# Enclosure_85x58_PBC-AW.net
KiCad netlist of a schematic drawn in EAGLE
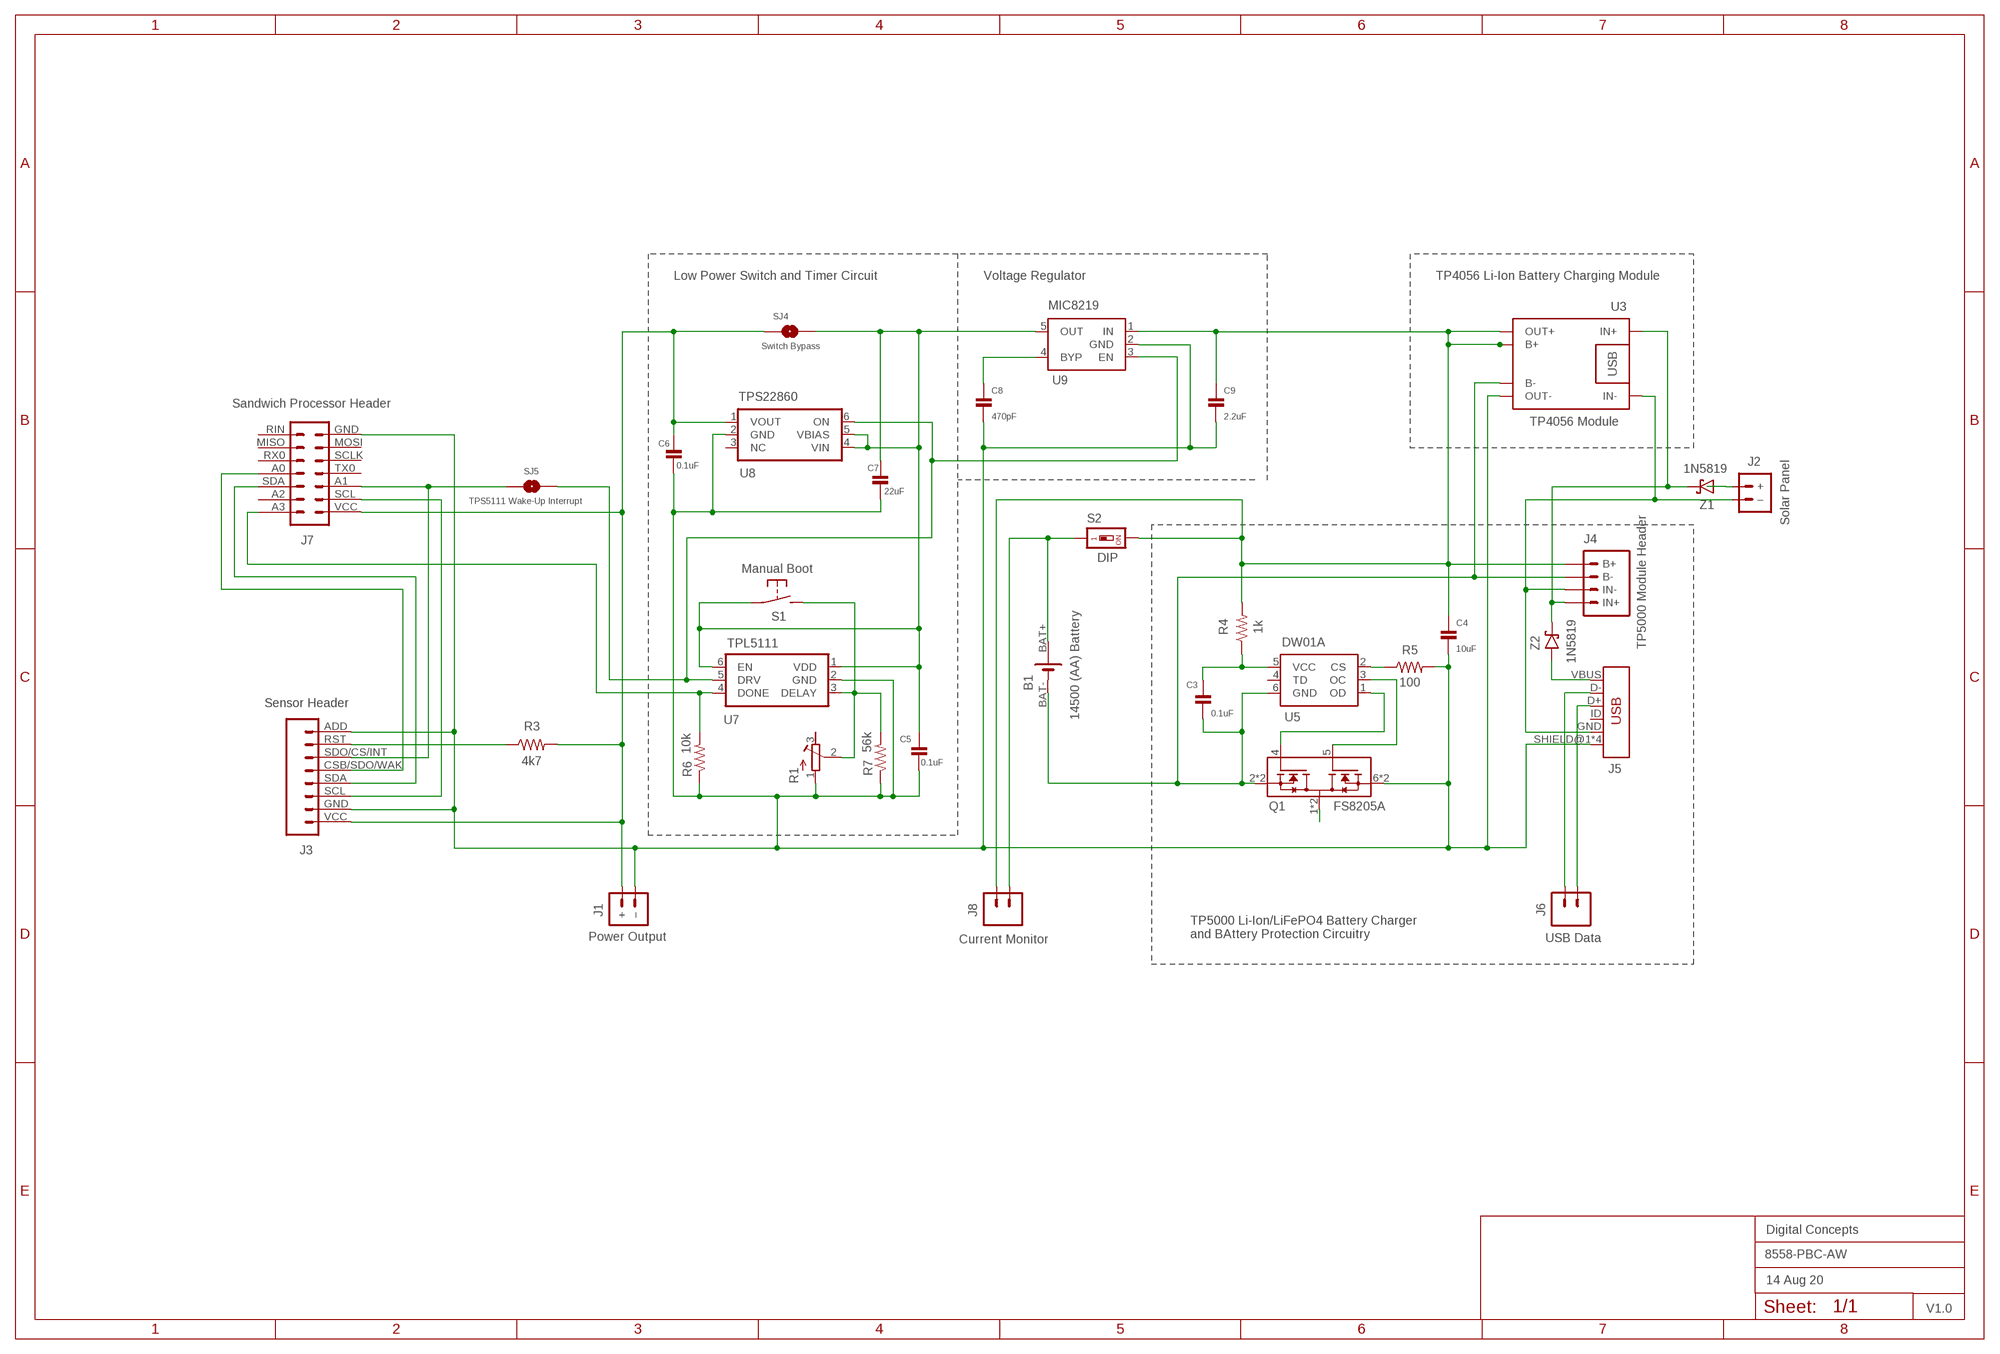
[diagram p0: schematic, sheet 1]

(export (version "E")
  (design (tool "Eeschema 10.0.6"))
  (components
    (comp (ref "B1")
      (value "14500 (AA) Battery")
      (footprint "eagle-import:BATTERY-14500")
      (libsource (lib "eagle-import") (part "BATTERY-HOLDER-14500(AA)"))
    )
    (comp (ref "C3")
      (value "0.1uF")
      (footprint "eagle-import:C0805")
      (libsource (lib "eagle-import") (part "CAPACITOR"))
    )
    (comp (ref "C4")
      (value "10uF")
      (footprint "eagle-import:C0805")
      (libsource (lib "eagle-import") (part "CAPACITOR"))
    )
    (comp (ref "C5")
      (value "0.1uF")
      (footprint "eagle-import:C0805")
      (libsource (lib "eagle-import") (part "CAPACITOR"))
    )
    (comp (ref "C6")
      (value "0.1uF")
      (footprint "eagle-import:C0805")
      (libsource (lib "eagle-import") (part "CAPACITOR"))
    )
    (comp (ref "C7")
      (value "22uF")
      (footprint "eagle-import:C0805")
      (libsource (lib "eagle-import") (part "CAPACITOR"))
    )
    (comp (ref "C8")
      (value "470pF")
      (footprint "eagle-import:C0805")
      (libsource (lib "eagle-import") (part "CAPACITOR"))
    )
    (comp (ref "C9")
      (value "2.2uF")
      (footprint "eagle-import:C0805")
      (libsource (lib "eagle-import") (part "CAPACITOR"))
    )
    (comp (ref "J1")
      (value "Power Output")
      (footprint "eagle-import:JST-PH1.25")
      (libsource (lib "eagle-import") (part "JST-PH1.25-MALE"))
    )
    (comp (ref "J2")
      (value "Solar Panel")
      (footprint "eagle-import:JST-PH2.0")
      (libsource (lib "eagle-import") (part "JST-PH2.0-MALE"))
    )
    (comp (ref "J3")
      (value "Sensor Header")
      (footprint "eagle-import:CONN_08-SENSOR")
      (libsource (lib "eagle-import") (part "HEADER-1X8-SENSOR"))
    )
    (comp (ref "J4")
      (value "TP5000 Module Header")
      (footprint "eagle-import:CONN_04-GENERIC")
      (libsource (lib "eagle-import") (part "TP5000-MODULE"))
    )
    (comp (ref "J5")
      (value "USB")
      (footprint "eagle-import:USB-MINIB")
      (libsource (lib "eagle-import") (part "USB_MINI-B_SMT"))
    )
    (comp (ref "J6")
      (value "USB Data")
      (footprint "eagle-import:CONN_02-GENERIC")
      (libsource (lib "eagle-import") (part "1X2-PIN-HEADER"))
    )
    (comp (ref "J7")
      (value "Sandwich Processor Header")
      (footprint "eagle-import:CONN_2X7-WIJNAND-PROCESSOR")
      (libsource (lib "eagle-import") (part "HEADER-2X7-SANDWICH-PROCESSOR"))
    )
    (comp (ref "J8")
      (value "JST-PH2.0-MALE-HORIZONTALJST-PTH-2")
      (footprint "eagle-import:JST-2-PTH")
      (libsource (lib "eagle-import") (part "JST-PH2.0-MALE-HORIZONTALJST-PTH-2"))
    )
    (comp (ref "Q1")
      (value "FS8205A")
      (footprint "eagle-import:SOP65P640X120-8N")
      (fields (field (name "MF") "Fortune Semiconductor"))
      (libsource (lib "eagle-import") (part "FS8205A"))
    )
    (comp (ref "R1")
      (value "RESISTOR-TRIMM64W")
      (footprint "eagle-import:RTRIM64W")
      (libsource (lib "eagle-import") (part "RESISTOR-TRIMM64W"))
    )
    (comp (ref "R3")
      (value "4k7")
      (footprint "eagle-import:R0805")
      (libsource (lib "eagle-import") (part "RESISTORR0805"))
    )
    (comp (ref "R4")
      (value "1k")
      (footprint "eagle-import:R0805")
      (libsource (lib "eagle-import") (part "RESISTORR0805"))
    )
    (comp (ref "R5")
      (value "100")
      (footprint "eagle-import:R0805")
      (libsource (lib "eagle-import") (part "RESISTORR0805"))
    )
    (comp (ref "R6")
      (value "10k")
      (footprint "eagle-import:R0805")
      (libsource (lib "eagle-import") (part "RESISTORR0805"))
    )
    (comp (ref "R7")
      (value "56k")
      (footprint "eagle-import:R0805")
      (libsource (lib "eagle-import") (part "RESISTORR0805"))
    )
    (comp (ref "S1")
      (value "Manual Boot")
      (footprint "eagle-import:SWITCH-2-PAD")
      (libsource (lib "eagle-import") (part "MOMENTARY-SWITCH-2-PIN"))
    )
    (comp (ref "S2")
      (value "DIP")
      (footprint "eagle-import:SMS-001")
      (libsource (lib "eagle-import") (part "SWITCH-DIP-SWS001"))
    )
    (comp (ref "SJ4")
      (value "Switch Bypass")
      (footprint "eagle-import:SJ")
      (libsource (lib "eagle-import") (part "SJ"))
    )
    (comp (ref "SJ5")
      (value "TPS5111 Wake-Up Interrupt")
      (footprint "eagle-import:SJ")
      (libsource (lib "eagle-import") (part "SJ"))
    )
    (comp (ref "U3")
      (value "TP4056 Module")
      (footprint "eagle-import:BATTERY-CHARGER-LI-PROT")
      (libsource (lib "eagle-import") (part "BATTERY-CHARGER-LI-PROT"))
    )
    (comp (ref "U5")
      (value "DW01A")
      (footprint "eagle-import:SOT23-6")
      (fields (field (name "MF") "Fortune Semiconductor"))
      (libsource (lib "eagle-import") (part "DW01A"))
    )
    (comp (ref "U7")
      (value "TPL5111")
      (footprint "eagle-import:SOT-23-6")
      (libsource (lib "eagle-import") (part "TPL5111DDCR"))
    )
    (comp (ref "U8")
      (value "TPS22860")
      (footprint "eagle-import:SOT-23-6")
      (libsource (lib "eagle-import") (part "TPS22860"))
    )
    (comp (ref "U9")
      (value "MIC8219")
      (footprint "eagle-import:SOT-23-5")
      (libsource (lib "eagle-import") (part "MIC5219XX"))
    )
    (comp (ref "Z1")
      (value "1N5819")
      (footprint "eagle-import:SOD-123")
      (libsource (lib "eagle-import") (part "1N5819-SOD-123"))
    )
    (comp (ref "Z2")
      (value "1N5819")
      (footprint "eagle-import:SOD-123")
      (libsource (lib "eagle-import") (part "1N5819-SOD-123"))
    )
  )
  (nets
    (net (code "1") (name "Net-(B1-PadBAT+)") (class "Default")
      (node (ref "B1") (pin "BAT+") (pinfunction "BAT+_BAT+") (pintype "power_in"))
      (node (ref "J8") (pin "2") (pinfunction "2_2") (pintype "passive"))
      (node (ref "S2") (pin "1") (pinfunction "1_1") (pintype "passive"))
    )
    (net (code "2") (name "Net-(J1-–)") (class "Default")
      (node (ref "C4") (pin "2") (pinfunction "2_2") (pintype "passive"))
      (node (ref "C5") (pin "2") (pinfunction "2_2") (pintype "passive"))
      (node (ref "C6") (pin "2") (pinfunction "2_2") (pintype "passive"))
      (node (ref "C7") (pin "2") (pinfunction "2_2") (pintype "passive"))
      (node (ref "C8") (pin "2") (pinfunction "2_2") (pintype "passive"))
      (node (ref "C9") (pin "2") (pinfunction "2_2") (pintype "passive"))
      (node (ref "J1") (pin "-") (pinfunction "–_-") (pintype "power_in"))
      (node (ref "J3") (pin "ADD") (pinfunction "8_ADD") (pintype "passive"))
      (node (ref "J3") (pin "GND") (pinfunction "2_GND") (pintype "passive"))
      (node (ref "J5") (pin "SHIELD@1") (pinfunction "SHIELD_SHIELD@1") (pintype "power_in"))
      (node (ref "J5") (pin "SHIELD@2") (pinfunction "SHIELD_SHIELD@2") (pintype "power_in"))
      (node (ref "J5") (pin "SHIELD@3") (pinfunction "SHIELD_SHIELD@3") (pintype "power_in"))
      (node (ref "J5") (pin "SHIELD@4") (pinfunction "SHIELD_SHIELD@4") (pintype "power_in"))
      (node (ref "J7") (pin "GND") (pinfunction "7_GND") (pintype "passive"))
      (node (ref "Q1") (pin "6") (pinfunction "S2_6") (pintype "passive"))
      (node (ref "Q1") (pin "7") (pinfunction "S2_7") (pintype "passive"))
      (node (ref "R1") (pin "1") (pinfunction "A_1") (pintype "passive"))
      (node (ref "R5") (pin "2") (pinfunction "2_2") (pintype "passive"))
      (node (ref "R6") (pin "1") (pinfunction "1_1") (pintype "passive"))
      (node (ref "R7") (pin "1") (pinfunction "1_1") (pintype "passive"))
      (node (ref "U3") (pin "OUT-") (pinfunction "OUT-_OUT-") (pintype "power_in"))
      (node (ref "U7") (pin "2") (pinfunction "GND_2") (pintype "power_in"))
      (node (ref "U8") (pin "2") (pinfunction "GND_2") (pintype "power_in"))
      (node (ref "U9") (pin "2") (pinfunction "GND_2") (pintype "power_in"))
    )
    (net (code "3") (name "Net-(J2-Pad+)") (class "Default")
      (node (ref "J2") (pin "+") (pinfunction "+_+") (pintype "power_in"))
      (node (ref "Z1") (pin "A") (pinfunction "A_A") (pintype "passive"))
    )
    (net (code "4") (name "Net-(J2-–)") (class "Default")
      (node (ref "J2") (pin "-") (pinfunction "–_-") (pintype "power_in"))
      (node (ref "J4") (pin "2") (pinfunction "IN-_2") (pintype "passive"))
      (node (ref "J5") (pin "GND") (pinfunction "GND_GND") (pintype "power_in"))
      (node (ref "U3") (pin "IN-") (pinfunction "IN-_IN-") (pintype "power_in"))
    )
    (net (code "5") (name "Net-(J3-1)") (class "Default")
      (node (ref "C6") (pin "1") (pinfunction "1_1") (pintype "passive"))
      (node (ref "J1") (pin "+") (pinfunction "+_+") (pintype "power_in"))
      (node (ref "J3") (pin "VCC") (pinfunction "1_VCC") (pintype "passive"))
      (node (ref "J7") (pin "VCC") (pinfunction "1_VCC") (pintype "passive"))
      (node (ref "R3") (pin "2") (pinfunction "2_2") (pintype "passive"))
      (node (ref "SJ4") (pin "1") (pinfunction "1_1") (pintype "passive"))
      (node (ref "U8") (pin "1") (pinfunction "VOUT_1") (pintype "power_in"))
    )
    (net (code "6") (name "Net-(J3-3)") (class "Default")
      (node (ref "J3") (pin "SCL") (pinfunction "3_SCL") (pintype "passive"))
      (node (ref "J7") (pin "SCL") (pinfunction "2_SCL") (pintype "passive"))
    )
    (net (code "7") (name "Net-(J3-4)") (class "Default")
      (node (ref "J3") (pin "SDA") (pinfunction "4_SDA") (pintype "passive"))
      (node (ref "J7") (pin "SDA") (pinfunction "12_SDA") (pintype "passive"))
    )
    (net (code "8") (name "Net-(J3-5)") (class "Default")
      (node (ref "J3") (pin "CSB/SDO/WAK") (pinfunction "5_CSB/SDO/WAK") (pintype "passive"))
      (node (ref "J7") (pin "A0") (pinfunction "11_A0") (pintype "passive"))
    )
    (net (code "9") (name "Net-(J3-6)") (class "Default")
      (node (ref "J3") (pin "SDO/CS/INT") (pinfunction "6_SDO/CS/INT") (pintype "passive"))
      (node (ref "J7") (pin "A1") (pinfunction "3_A1") (pintype "passive"))
      (node (ref "SJ5") (pin "1") (pinfunction "1_1") (pintype "passive"))
    )
    (net (code "10") (name "Net-(J3-7)") (class "Default")
      (node (ref "J3") (pin "RST") (pinfunction "7_RST") (pintype "passive"))
      (node (ref "R3") (pin "1") (pinfunction "1_1") (pintype "passive"))
    )
    (net (code "11") (name "Net-(J4-B+)") (class "Default")
      (node (ref "C4") (pin "1") (pinfunction "1_1") (pintype "passive"))
      (node (ref "C9") (pin "1") (pinfunction "1_1") (pintype "passive"))
      (node (ref "J4") (pin "4") (pinfunction "B+_4") (pintype "passive"))
      (node (ref "J8") (pin "1") (pinfunction "1_1") (pintype "passive"))
      (node (ref "R4") (pin "2") (pinfunction "2_2") (pintype "passive"))
      (node (ref "S2") (pin "2") (pinfunction "2_2") (pintype "passive"))
      (node (ref "U3") (pin "B+") (pinfunction "B+_B+") (pintype "power_in"))
      (node (ref "U3") (pin "OUT+") (pinfunction "OUT+_OUT+") (pintype "power_in"))
      (node (ref "U9") (pin "1") (pinfunction "IN_1") (pintype "power_in"))
    )
    (net (code "12") (name "Net-(J4-B-)") (class "Default")
      (node (ref "B1") (pin "BAT-") (pinfunction "BAT-_BAT-") (pintype "power_in"))
      (node (ref "C3") (pin "2") (pinfunction "2_2") (pintype "passive"))
      (node (ref "J4") (pin "3") (pinfunction "B-_3") (pintype "passive"))
      (node (ref "Q1") (pin "2") (pinfunction "S1_2") (pintype "passive"))
      (node (ref "Q1") (pin "3") (pinfunction "S1_3") (pintype "passive"))
      (node (ref "U3") (pin "B-") (pinfunction "B-_B-") (pintype "power_in"))
      (node (ref "U5") (pin "6") (pinfunction "GND_6") (pintype "power_in"))
    )
    (net (code "13") (name "Net-(J4-IN+)") (class "Default")
      (node (ref "J4") (pin "1") (pinfunction "IN+_1") (pintype "passive"))
      (node (ref "U3") (pin "IN+") (pinfunction "IN+_IN+") (pintype "power_in"))
      (node (ref "Z1") (pin "C") (pinfunction "C_C") (pintype "passive"))
      (node (ref "Z2") (pin "C") (pinfunction "C_C") (pintype "passive"))
    )
    (net (code "14") (name "Net-(J5-PadD+)") (class "Default")
      (node (ref "J5") (pin "D+") (pinfunction "D+_D+") (pintype "bidirectional"))
      (node (ref "J6") (pin "2") (pinfunction "2_2") (pintype "passive"))
    )
    (net (code "15") (name "Net-(J5-PadD-)") (class "Default")
      (node (ref "J5") (pin "D-") (pinfunction "D-_D-") (pintype "bidirectional"))
      (node (ref "J6") (pin "1") (pinfunction "1_1") (pintype "passive"))
    )
    (net (code "16") (name "Net-(J5-PadVBUS)") (class "Default")
      (node (ref "J5") (pin "VBUS") (pinfunction "VBUS_VBUS") (pintype "power_in"))
      (node (ref "Z2") (pin "A") (pinfunction "A_A") (pintype "passive"))
    )
    (net (code "17") (name "Net-(J7-14)") (class "Default")
      (node (ref "J7") (pin "A3") (pinfunction "14_A3") (pintype "passive"))
      (node (ref "R6") (pin "2") (pinfunction "2_2") (pintype "passive"))
      (node (ref "U7") (pin "4") (pinfunction "DONE_4") (pintype "input"))
    )
    (net (code "18") (name "Net-(Q1-D12-Pad1)") (class "Default")
      (node (ref "Q1") (pin "1") (pinfunction "D12_1") (pintype "passive"))
      (node (ref "Q1") (pin "8") (pinfunction "D12_8") (pintype "passive"))
    )
    (net (code "19") (name "Net-(Q1-G1)") (class "Default")
      (node (ref "Q1") (pin "4") (pinfunction "G1_4") (pintype "passive"))
      (node (ref "U5") (pin "1") (pinfunction "OD_1") (pintype "bidirectional"))
    )
    (net (code "20") (name "Net-(Q1-G2)") (class "Default")
      (node (ref "Q1") (pin "5") (pinfunction "G2_5") (pintype "passive"))
      (node (ref "U5") (pin "3") (pinfunction "OC_3") (pintype "bidirectional"))
    )
    (net (code "21") (name "Net-(R1-S)") (class "Default")
      (node (ref "R1") (pin "2") (pinfunction "S_2") (pintype "passive"))
      (node (ref "R7") (pin "2") (pinfunction "2_2") (pintype "passive"))
      (node (ref "S1") (pin "P$2") (pinfunction "S_P$2") (pintype "passive"))
      (node (ref "U7") (pin "3") (pinfunction "DELAY_3") (pintype "input"))
    )
    (net (code "22") (name "Net-(S1-P)") (class "Default")
      (node (ref "C5") (pin "1") (pinfunction "1_1") (pintype "passive"))
      (node (ref "C7") (pin "1") (pinfunction "1_1") (pintype "passive"))
      (node (ref "S1") (pin "P$1") (pinfunction "P_P$1") (pintype "passive"))
      (node (ref "SJ4") (pin "2") (pinfunction "2_2") (pintype "passive"))
      (node (ref "U7") (pin "1") (pinfunction "VDD_1") (pintype "power_in"))
      (node (ref "U7") (pin "6") (pinfunction "EN_6") (pintype "input"))
      (node (ref "U8") (pin "4") (pinfunction "VIN_4") (pintype "power_in"))
      (node (ref "U8") (pin "5") (pinfunction "VBIAS_5") (pintype "input"))
      (node (ref "U9") (pin "5") (pinfunction "OUT_5") (pintype "power_in"))
    )
    (net (code "23") (name "Net-(U5-CS)") (class "Default")
      (node (ref "R5") (pin "1") (pinfunction "1_1") (pintype "passive"))
      (node (ref "U5") (pin "2") (pinfunction "CS_2") (pintype "bidirectional"))
    )
    (net (code "24") (name "Net-(U5-VCC)") (class "Default")
      (node (ref "C3") (pin "1") (pinfunction "1_1") (pintype "passive"))
      (node (ref "R4") (pin "1") (pinfunction "1_1") (pintype "passive"))
      (node (ref "U5") (pin "5") (pinfunction "VCC_5") (pintype "power_in"))
    )
    (net (code "25") (name "Net-(U7-DRV)") (class "Default")
      (node (ref "SJ5") (pin "2") (pinfunction "2_2") (pintype "passive"))
      (node (ref "U7") (pin "5") (pinfunction "DRV_5") (pintype "output"))
      (node (ref "U8") (pin "6") (pinfunction "ON_6") (pintype "input"))
      (node (ref "U9") (pin "3") (pinfunction "EN_3") (pintype "input"))
    )
    (net (code "26") (name "Net-(U9-BYP)") (class "Default")
      (node (ref "C8") (pin "1") (pinfunction "1_1") (pintype "passive"))
      (node (ref "U9") (pin "4") (pinfunction "BYP_4") (pintype "passive"))
    )
    (net (code "27") (name "unconnected-(J5-PadID)") (class "Default")
      (node (ref "J5") (pin "ID") (pinfunction "ID_ID") (pintype "bidirectional"))
    )
    (net (code "28") (name "unconnected-(J7-4-PadTX0)") (class "Default")
      (node (ref "J7") (pin "TX0") (pinfunction "4_TX0") (pintype "passive"))
    )
    (net (code "29") (name "unconnected-(J7-5-PadSCLK)") (class "Default")
      (node (ref "J7") (pin "SCLK") (pinfunction "5_SCLK") (pintype "passive"))
    )
    (net (code "30") (name "unconnected-(J7-6-PadMOSI)") (class "Default")
      (node (ref "J7") (pin "MOSI") (pinfunction "6_MOSI") (pintype "passive"))
    )
    (net (code "31") (name "unconnected-(J7-8-PadRIN)") (class "Default")
      (node (ref "J7") (pin "RIN") (pinfunction "8_RIN") (pintype "passive"))
    )
    (net (code "32") (name "unconnected-(J7-9-PadMISO)") (class "Default")
      (node (ref "J7") (pin "MISO") (pinfunction "9_MISO") (pintype "passive"))
    )
    (net (code "33") (name "unconnected-(J7-10-PadRX0)") (class "Default")
      (node (ref "J7") (pin "RX0") (pinfunction "10_RX0") (pintype "passive"))
    )
    (net (code "34") (name "unconnected-(J7-13-PadA2)") (class "Default")
      (node (ref "J7") (pin "A2") (pinfunction "13_A2") (pintype "passive"))
    )
    (net (code "35") (name "unconnected-(R1-E-Pad3)") (class "Default")
      (node (ref "R1") (pin "3") (pinfunction "E_3") (pintype "passive"))
    )
    (net (code "36") (name "unconnected-(U5-TD-Pad4)") (class "Default")
      (node (ref "U5") (pin "4") (pinfunction "TD_4") (pintype "bidirectional"))
    )
    (net (code "37") (name "unconnected-(U8-NC-Pad3)") (class "Default")
      (node (ref "U8") (pin "3") (pinfunction "NC_3") (pintype "no_connect"))
    )
  )
)
